# wally.net
KiCad netlist of a schematic drawn in EAGLE
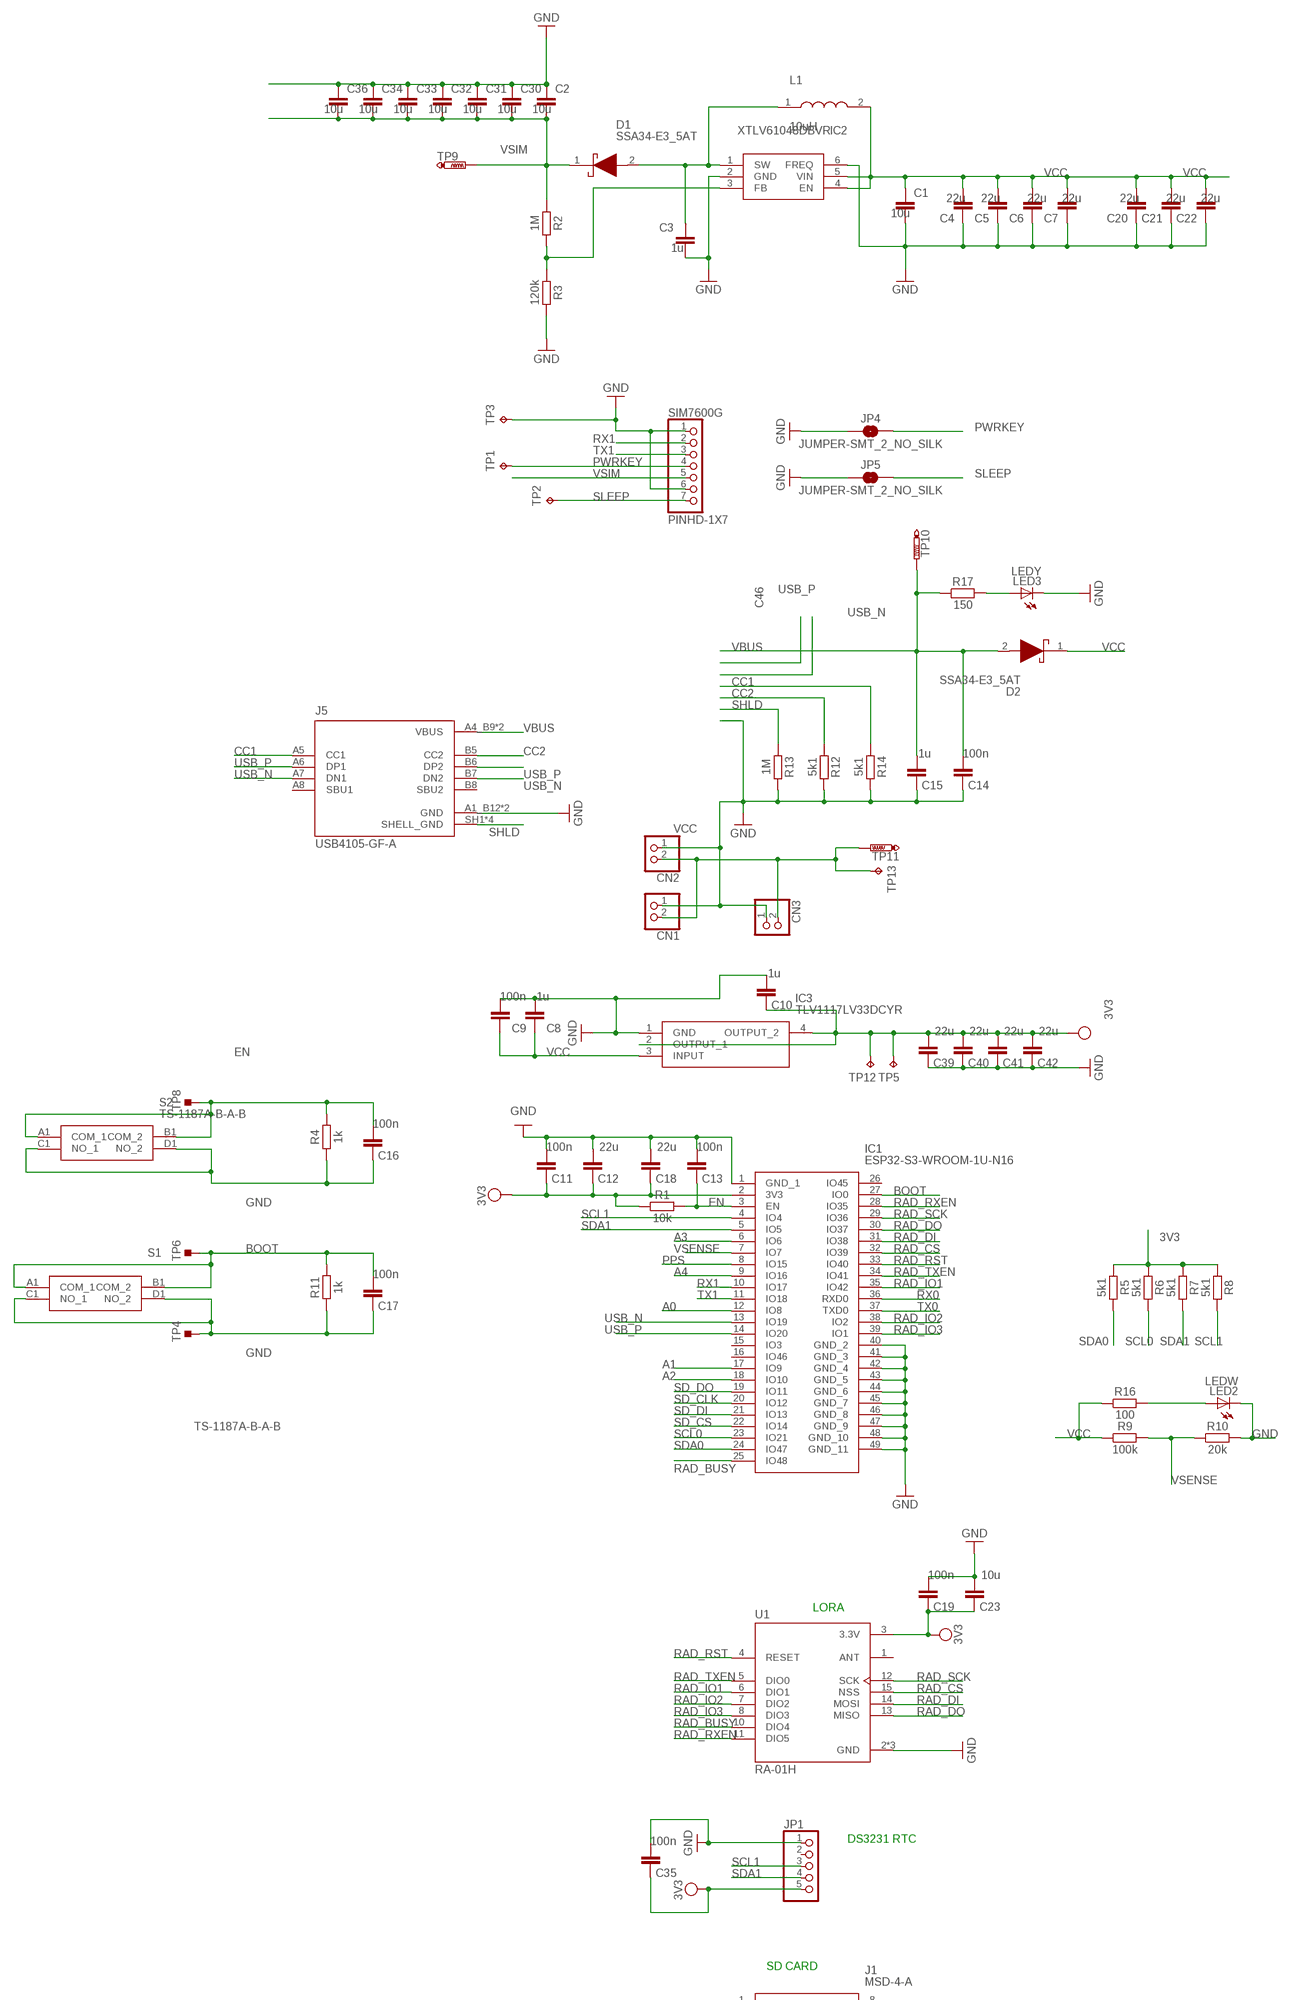
[diagram p0: schematic, sheet 1, part 1 of 2]
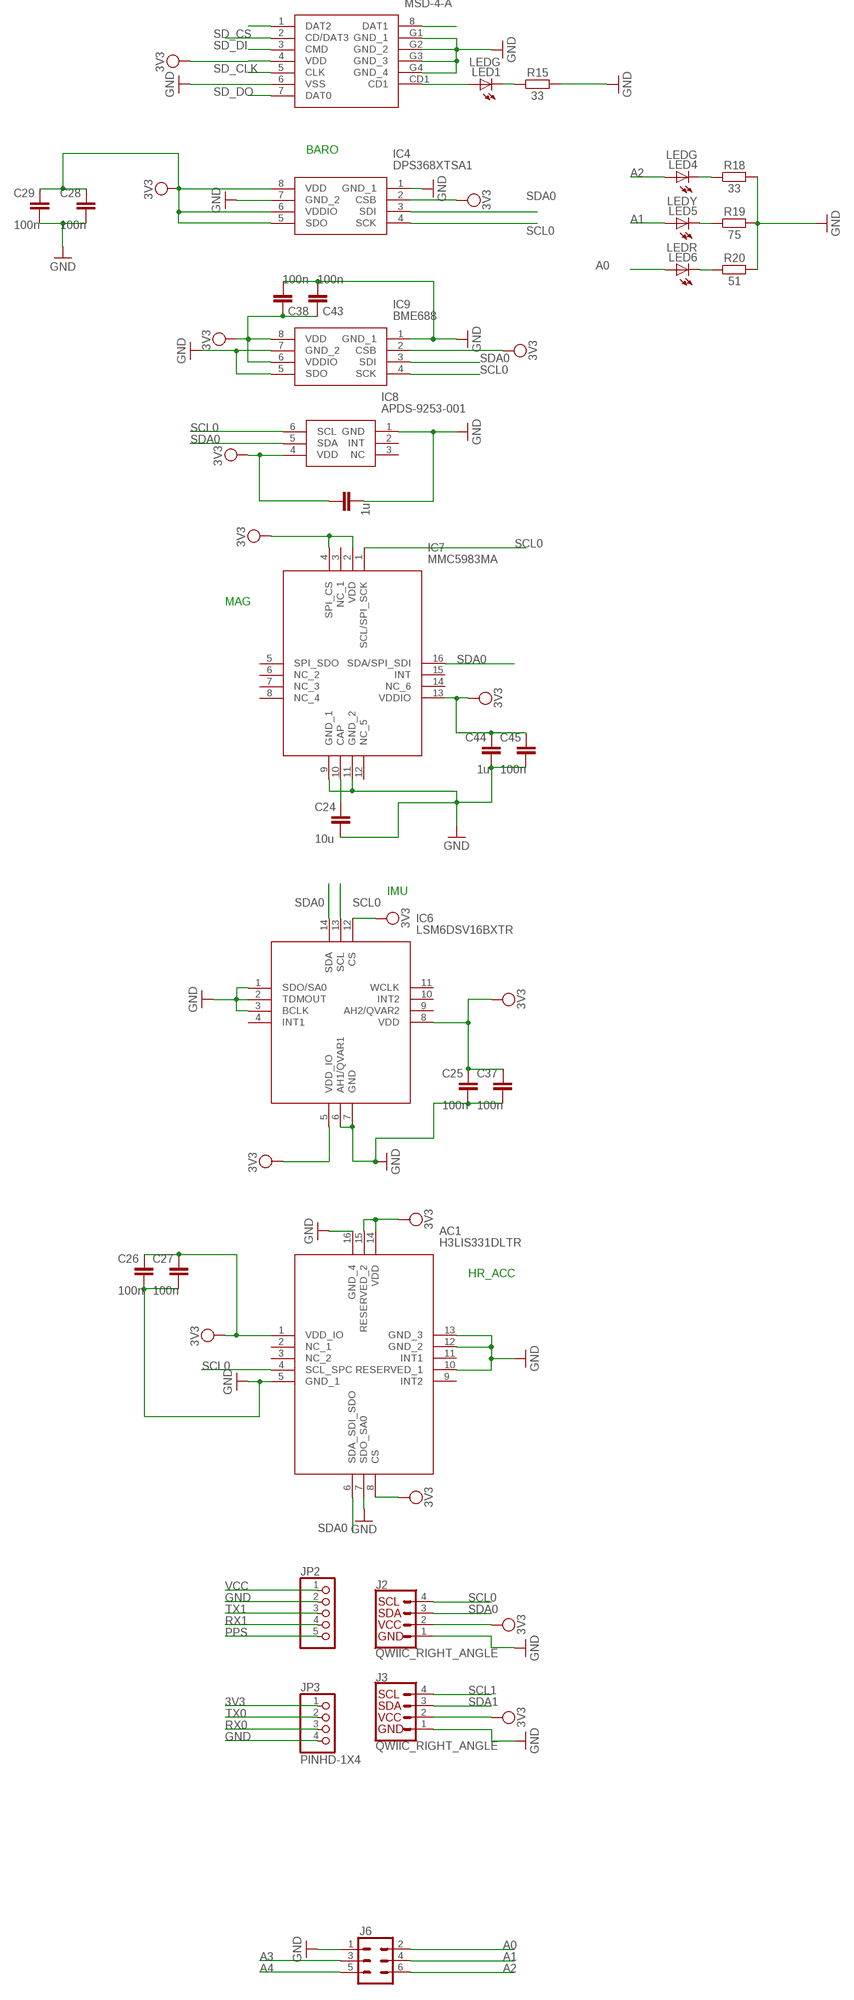
[diagram p1: schematic, sheet 1, part 2 of 2]

(export (version "E")
  (design (tool "Eeschema 10.0.6"))
  (components
    (comp (ref "AC1")
      (value "H3LIS331DLTR")
      (footprint "eagle-import:LIS3DHTR")
      (fields (field (name "MOUSER_PART_NUMBER") "511-H3LIS331DLTR"))
      (libsource (lib "eagle-import") (part "H3LIS331DLTR"))
    )
    (comp (ref "C1")
      (value "10u")
      (footprint "eagle-import:CAPC1005X60")
      (libsource (lib "eagle-import") (part "CCHIP-0402(1005-METRIC)_"))
    )
    (comp (ref "C2")
      (value "10u")
      (footprint "eagle-import:CAPC1608X85")
      (libsource (lib "eagle-import") (part "CCHIP-0603(1608-METRIC)_"))
    )
    (comp (ref "C3")
      (value "1u")
      (footprint "eagle-import:CAPC1005X60")
      (libsource (lib "eagle-import") (part "CCHIP-0402(1005-METRIC)_"))
    )
    (comp (ref "C4")
      (value "22u")
      (footprint "eagle-import:CAPC1608X85")
      (libsource (lib "eagle-import") (part "CCHIP-0603(1608-METRIC)_"))
    )
    (comp (ref "C5")
      (value "22u")
      (footprint "eagle-import:CAPC1608X85")
      (libsource (lib "eagle-import") (part "CCHIP-0603(1608-METRIC)_"))
    )
    (comp (ref "C6")
      (value "22u")
      (footprint "eagle-import:CAPC1608X85")
      (libsource (lib "eagle-import") (part "CCHIP-0603(1608-METRIC)_"))
    )
    (comp (ref "C7")
      (value "22u")
      (footprint "eagle-import:CAPC1608X85")
      (libsource (lib "eagle-import") (part "CCHIP-0603(1608-METRIC)_"))
    )
    (comp (ref "C8")
      (value "1u")
      (footprint "eagle-import:CAPC1005X60")
      (libsource (lib "eagle-import") (part "CCHIP-0402(1005-METRIC)_"))
    )
    (comp (ref "C9")
      (value "100n")
      (footprint "eagle-import:CAPC1005X60")
      (libsource (lib "eagle-import") (part "CCHIP-0402(1005-METRIC)_"))
    )
    (comp (ref "C10")
      (value "1u")
      (footprint "eagle-import:CAPC1005X60")
      (libsource (lib "eagle-import") (part "CCHIP-0402(1005-METRIC)_"))
    )
    (comp (ref "C11")
      (value "100n")
      (footprint "eagle-import:CAPC1005X60")
      (libsource (lib "eagle-import") (part "CCHIP-0402(1005-METRIC)_"))
    )
    (comp (ref "C12")
      (value "22u")
      (footprint "eagle-import:CAPC1608X85")
      (libsource (lib "eagle-import") (part "CCHIP-0603(1608-METRIC)_"))
    )
    (comp (ref "C13")
      (value "100n")
      (footprint "eagle-import:CAPC1005X60")
      (libsource (lib "eagle-import") (part "CCHIP-0402(1005-METRIC)_"))
    )
    (comp (ref "C14")
      (value "100n")
      (footprint "eagle-import:CAPC1005X60")
      (libsource (lib "eagle-import") (part "CCHIP-0402(1005-METRIC)_"))
    )
    (comp (ref "C15")
      (value "1u")
      (footprint "eagle-import:CAPC1005X60")
      (libsource (lib "eagle-import") (part "CCHIP-0402(1005-METRIC)_"))
    )
    (comp (ref "C16")
      (value "100n")
      (footprint "eagle-import:CAPC1005X60")
      (libsource (lib "eagle-import") (part "CCHIP-0402(1005-METRIC)_"))
    )
    (comp (ref "C17")
      (value "100n")
      (footprint "eagle-import:CAPC1005X60")
      (libsource (lib "eagle-import") (part "CCHIP-0402(1005-METRIC)_"))
    )
    (comp (ref "C18")
      (value "22u")
      (footprint "eagle-import:CAPC1608X85")
      (libsource (lib "eagle-import") (part "CCHIP-0603(1608-METRIC)_"))
    )
    (comp (ref "C19")
      (value "100n")
      (footprint "eagle-import:CAPC1005X60")
      (libsource (lib "eagle-import") (part "CCHIP-0402(1005-METRIC)_"))
    )
    (comp (ref "C20")
      (value "22u")
      (footprint "eagle-import:CAPC1608X85")
      (libsource (lib "eagle-import") (part "CCHIP-0603(1608-METRIC)_"))
    )
    (comp (ref "C21")
      (value "22u")
      (footprint "eagle-import:CAPC1608X85")
      (libsource (lib "eagle-import") (part "CCHIP-0603(1608-METRIC)_"))
    )
    (comp (ref "C22")
      (value "22u")
      (footprint "eagle-import:CAPC1608X85")
      (libsource (lib "eagle-import") (part "CCHIP-0603(1608-METRIC)_"))
    )
    (comp (ref "C23")
      (value "10u")
      (footprint "eagle-import:CAPC1005X60")
      (libsource (lib "eagle-import") (part "CCHIP-0402(1005-METRIC)_"))
    )
    (comp (ref "C24")
      (value "10u")
      (footprint "eagle-import:CAPC1005X60")
      (libsource (lib "eagle-import") (part "CCHIP-0402(1005-METRIC)_"))
    )
    (comp (ref "C25")
      (value "100n")
      (footprint "eagle-import:CAPC1005X60")
      (libsource (lib "eagle-import") (part "CCHIP-0402(1005-METRIC)_"))
    )
    (comp (ref "C26")
      (value "100n")
      (footprint "eagle-import:CAPC1005X60")
      (libsource (lib "eagle-import") (part "CCHIP-0402(1005-METRIC)_"))
    )
    (comp (ref "C27")
      (value "100n")
      (footprint "eagle-import:CAPC1005X60")
      (libsource (lib "eagle-import") (part "CCHIP-0402(1005-METRIC)_"))
    )
    (comp (ref "C28")
      (value "100n")
      (footprint "eagle-import:CAPC1005X60")
      (libsource (lib "eagle-import") (part "CCHIP-0402(1005-METRIC)_"))
    )
    (comp (ref "C29")
      (value "100n")
      (footprint "eagle-import:CAPC1005X60")
      (libsource (lib "eagle-import") (part "CCHIP-0402(1005-METRIC)_"))
    )
    (comp (ref "C30")
      (value "10u")
      (footprint "eagle-import:CAPC1608X85")
      (libsource (lib "eagle-import") (part "CCHIP-0603(1608-METRIC)_"))
    )
    (comp (ref "C31")
      (value "10u")
      (footprint "eagle-import:CAPC1608X85")
      (libsource (lib "eagle-import") (part "CCHIP-0603(1608-METRIC)_"))
    )
    (comp (ref "C32")
      (value "10u")
      (footprint "eagle-import:CAPC1608X85")
      (libsource (lib "eagle-import") (part "CCHIP-0603(1608-METRIC)_"))
    )
    (comp (ref "C33")
      (value "10u")
      (footprint "eagle-import:CAPC1608X85")
      (libsource (lib "eagle-import") (part "CCHIP-0603(1608-METRIC)_"))
    )
    (comp (ref "C34")
      (value "10u")
      (footprint "eagle-import:CAPC1608X85")
      (libsource (lib "eagle-import") (part "CCHIP-0603(1608-METRIC)_"))
    )
    (comp (ref "C35")
      (value "100n")
      (footprint "eagle-import:CAPC1005X60")
      (libsource (lib "eagle-import") (part "CCHIP-0402(1005-METRIC)_"))
    )
    (comp (ref "C36")
      (value "10u")
      (footprint "eagle-import:CAPC1608X85")
      (libsource (lib "eagle-import") (part "CCHIP-0603(1608-METRIC)_"))
    )
    (comp (ref "C37")
      (value "100n")
      (footprint "eagle-import:CAPC1005X60")
      (libsource (lib "eagle-import") (part "CCHIP-0402(1005-METRIC)_"))
    )
    (comp (ref "C38")
      (value "100n")
      (footprint "eagle-import:CAPC1005X60")
      (libsource (lib "eagle-import") (part "CCHIP-0402(1005-METRIC)_"))
    )
    (comp (ref "C39")
      (value "22u")
      (footprint "eagle-import:CAPC1608X85")
      (libsource (lib "eagle-import") (part "CCHIP-0603(1608-METRIC)_"))
    )
    (comp (ref "C40")
      (value "22u")
      (footprint "eagle-import:CAPC1608X85")
      (libsource (lib "eagle-import") (part "CCHIP-0603(1608-METRIC)_"))
    )
    (comp (ref "C41")
      (value "22u")
      (footprint "eagle-import:CAPC1608X85")
      (libsource (lib "eagle-import") (part "CCHIP-0603(1608-METRIC)_"))
    )
    (comp (ref "C42")
      (value "22u")
      (footprint "eagle-import:CAPC1608X85")
      (libsource (lib "eagle-import") (part "CCHIP-0603(1608-METRIC)_"))
    )
    (comp (ref "C43")
      (value "100n")
      (footprint "eagle-import:CAPC1005X60")
      (libsource (lib "eagle-import") (part "CCHIP-0402(1005-METRIC)_"))
    )
    (comp (ref "C44")
      (value "1u")
      (footprint "eagle-import:CAPC1005X60")
      (libsource (lib "eagle-import") (part "CCHIP-0402(1005-METRIC)_"))
    )
    (comp (ref "C45")
      (value "100n")
      (footprint "eagle-import:CAPC1005X60")
      (libsource (lib "eagle-import") (part "CCHIP-0402(1005-METRIC)_"))
    )
    (comp (ref "C46")
      (value "1u")
      (footprint "eagle-import:CAPC1005X60")
      (libsource (lib "eagle-import") (part "CCHIP-0402(1005-METRIC)_"))
    )
    (comp (ref "CN1")
      (value "JST_2PIN-THM-RA")
      (footprint "eagle-import:JST-PH-2-THM-RA")
      (libsource (lib "eagle-import") (part "JST_2PIN-THM-RA"))
    )
    (comp (ref "CN2")
      (value "JST_2PIN-THM-RA")
      (footprint "eagle-import:JST-PH-2-THM-RA")
      (libsource (lib "eagle-import") (part "JST_2PIN-THM-RA"))
    )
    (comp (ref "CN3")
      (value "JST_2PIN-THM-RA")
      (footprint "eagle-import:JST-PH-2-THM-RA")
      (libsource (lib "eagle-import") (part "JST_2PIN-THM-RA"))
    )
    (comp (ref "D1")
      (value "SSA34-E3_5AT")
      (footprint "eagle-import:DIOM5127X229N")
      (fields
        (field (name "ARROW_PART_NUMBER") "SSA34-E3/5AT")
        (field (name "MOUSER_PART_NUMBER") "625-SSA34-E3/5AT")
      )
      (libsource (lib "eagle-import") (part "SSA34-E3_5AT"))
    )
    (comp (ref "D2")
      (value "SSA34-E3_5AT")
      (footprint "eagle-import:DIOM5127X229N")
      (fields
        (field (name "ARROW_PART_NUMBER") "SSA34-E3/5AT")
        (field (name "MOUSER_PART_NUMBER") "625-SSA34-E3/5AT")
      )
      (libsource (lib "eagle-import") (part "SSA34-E3_5AT"))
    )
    (comp (ref "IC1")
      (value "ESP32-S3-WROOM-1U-N16")
      (footprint "eagle-import:ESP32S3WROOM1UN16")
      (fields (field (name "MOUSER_PART_NUMBER") "356-ESP32S3WROM1UN16"))
      (libsource (lib "eagle-import") (part "ESP32-S3-WROOM-1U-N16"))
    )
    (comp (ref "IC2")
      (value "XTLV61048DBVR")
      (footprint "eagle-import:SOT95P280X145-6N")
      (libsource (lib "eagle-import") (part "XTLV61048DBVR"))
    )
    (comp (ref "IC3")
      (value "TLV1117LV33DCYR")
      (footprint "eagle-import:SOT230P700X180-4N")
      (fields (field (name "MOUSER_PART_NUMBER") "595-TLV1117LV33DCYR"))
      (libsource (lib "eagle-import") (part "TLV1117LV33DCYR"))
    )
    (comp (ref "IC4")
      (value "DPS368XTSA1")
      (footprint "eagle-import:DPS368XTSA1")
      (fields (field (name "MOUSER_PART_NUMBER") "726-DPS368XTSA1"))
      (libsource (lib "eagle-import") (part "DPS368XTSA1"))
    )
    (comp (ref "IC6")
      (value "LSM6DSV16BXTR")
      (footprint "eagle-import:LSM6DSV16BXTR")
      (fields (field (name "MOUSER_PART_NUMBER") "511-LSM6DSV16BXTR"))
      (libsource (lib "eagle-import") (part "LSM6DSV16BXTR"))
    )
    (comp (ref "IC7")
      (value "MMC5983MA")
      (footprint "eagle-import:MMC5983MA")
      (fields (field (name "MOUSER_PART_NUMBER") "438-MMC5983MA"))
      (libsource (lib "eagle-import") (part "MMC5983MA"))
    )
    (comp (ref "IC8")
      (value "APDS-9253-001")
      (footprint "eagle-import:APDS9253001")
      (fields (field (name "MOUSER_PART_NUMBER") "630-APDS-9253-001"))
      (libsource (lib "eagle-import") (part "APDS-9253-001"))
    )
    (comp (ref "IC9")
      (value "BME688")
      (footprint "eagle-import:BME688")
      (fields (field (name "MOUSER_PART_NUMBER") "262-BME688"))
      (libsource (lib "eagle-import") (part "BME688"))
    )
    (comp (ref "J1")
      (value "MSD-4-A")
      (footprint "eagle-import:MSD4A")
      (fields (field (name "MOUSER_PART_NUMBER") "179-MSD-4-A"))
      (libsource (lib "eagle-import") (part "MSD-4-A"))
    )
    (comp (ref "J2")
      (value "QWIIC_RIGHT_ANGLE")
      (footprint "eagle-import:JST04_1MM_RA")
      (libsource (lib "eagle-import") (part "QWIIC_CONNECTORJS-1MM"))
    )
    (comp (ref "J3")
      (value "QWIIC_RIGHT_ANGLE")
      (footprint "eagle-import:JST04_1MM_RA")
      (libsource (lib "eagle-import") (part "QWIIC_CONNECTORJS-1MM"))
    )
    (comp (ref "J5")
      (value "USB4105-GF-A")
      (footprint "eagle-import:GCT_USB4105-GF-A")
      (fields
        (field (name "DIGIKEY_PART_NUMBER") "2073-USB4105-GF-ATR-ND")
        (field (name "MF") "Global Connector Technology")
        (field (name "MP") "USB4105GFA")
      )
      (libsource (lib "eagle-import") (part "USB4105-GF-A"))
    )
    (comp (ref "J6")
      (value "FEMALE 2x3")
      (footprint "eagle-import:2X3-NS")
      (libsource (lib "eagle-import") (part "CONN_03X2NO_SILK"))
    )
    (comp (ref "JP1")
      (value "PINHD-1X5")
      (footprint "eagle-import:1X05")
      (libsource (lib "eagle-import") (part "PINHD-1X5"))
    )
    (comp (ref "JP2")
      (value "PINHD-1X5")
      (footprint "eagle-import:1X05")
      (libsource (lib "eagle-import") (part "PINHD-1X5"))
    )
    (comp (ref "JP3")
      (value "PINHD-1X4")
      (footprint "eagle-import:1X04")
      (fields (field (name "MANUFACTURER") "Generic"))
      (libsource (lib "eagle-import") (part "PINHD-1X4"))
    )
    (comp (ref "JP4")
      (value "JUMPER-SMT_2_NO_SILK")
      (footprint "eagle-import:SMT-JUMPER_2_NO_SILK")
      (libsource (lib "eagle-import") (part "JUMPER-SMT_2_NO_SILK"))
    )
    (comp (ref "JP5")
      (value "JUMPER-SMT_2_NO_SILK")
      (footprint "eagle-import:SMT-JUMPER_2_NO_SILK")
      (libsource (lib "eagle-import") (part "JUMPER-SMT_2_NO_SILK"))
    )
    (comp (ref "L1")
      (value "10uH")
      (footprint "eagle-import:BMRF00060630100MA1")
      (fields (field (name "MANUFACTURER_PART_NUMBER") "BMRF00060630100MA1"))
      (libsource (lib "eagle-import") (part "BMRF00060630100MA1"))
    )
    (comp (ref "LED1")
      (value "LEDG")
      (footprint "eagle-import:CHIPLED_0805")
      (libsource (lib "eagle-import") (part "LEDCHIPLED_0805"))
    )
    (comp (ref "LED2")
      (value "LEDW")
      (footprint "eagle-import:CHIPLED_0805")
      (libsource (lib "eagle-import") (part "LEDCHIPLED_0805"))
    )
    (comp (ref "LED3")
      (value "LEDY")
      (footprint "eagle-import:CHIPLED_0805")
      (libsource (lib "eagle-import") (part "LEDCHIPLED_0805"))
    )
    (comp (ref "LED4")
      (value "LEDG")
      (footprint "eagle-import:CHIPLED_0805")
      (libsource (lib "eagle-import") (part "LEDCHIPLED_0805"))
    )
    (comp (ref "LED5")
      (value "LEDY")
      (footprint "eagle-import:CHIPLED_0805")
      (libsource (lib "eagle-import") (part "LEDCHIPLED_0805"))
    )
    (comp (ref "LED6")
      (value "LEDR")
      (footprint "eagle-import:CHIPLED_0805")
      (libsource (lib "eagle-import") (part "LEDCHIPLED_0805"))
    )
    (comp (ref "R1")
      (value "10k")
      (footprint "eagle-import:RESC1005X40")
      (libsource (lib "eagle-import") (part "RCHIP-0402(1005-METRIC)_"))
    )
    (comp (ref "R2")
      (value "1M")
      (footprint "eagle-import:RESC1608X60")
      (libsource (lib "eagle-import") (part "RCHIP-0603(1608-METRIC)_"))
    )
    (comp (ref "R3")
      (value "120k")
      (footprint "eagle-import:RESC1608X60")
      (libsource (lib "eagle-import") (part "RCHIP-0603(1608-METRIC)_"))
    )
    (comp (ref "R4")
      (value "1k")
      (footprint "eagle-import:RESC1005X40")
      (libsource (lib "eagle-import") (part "RCHIP-0402(1005-METRIC)_"))
    )
    (comp (ref "R5")
      (value "5k1")
      (footprint "eagle-import:RESC1005X40")
      (libsource (lib "eagle-import") (part "RCHIP-0402(1005-METRIC)_"))
    )
    (comp (ref "R6")
      (value "5k1")
      (footprint "eagle-import:RESC1005X40")
      (libsource (lib "eagle-import") (part "RCHIP-0402(1005-METRIC)_"))
    )
    (comp (ref "R7")
      (value "5k1")
      (footprint "eagle-import:RESC1005X40")
      (libsource (lib "eagle-import") (part "RCHIP-0402(1005-METRIC)_"))
    )
    (comp (ref "R8")
      (value "5k1")
      (footprint "eagle-import:RESC1005X40")
      (libsource (lib "eagle-import") (part "RCHIP-0402(1005-METRIC)_"))
    )
    (comp (ref "R9")
      (value "100k")
      (footprint "eagle-import:RESC1005X40")
      (libsource (lib "eagle-import") (part "RCHIP-0402(1005-METRIC)_"))
    )
    (comp (ref "R10")
      (value "20k")
      (footprint "eagle-import:RESC1005X40")
      (libsource (lib "eagle-import") (part "RCHIP-0402(1005-METRIC)_"))
    )
    (comp (ref "R11")
      (value "1k")
      (footprint "eagle-import:RESC1005X40")
      (libsource (lib "eagle-import") (part "RCHIP-0402(1005-METRIC)_"))
    )
    (comp (ref "R12")
      (value "5k1")
      (footprint "eagle-import:RESC1608X60")
      (libsource (lib "eagle-import") (part "RCHIP-0603(1608-METRIC)_"))
    )
    (comp (ref "R13")
      (value "1M")
      (footprint "eagle-import:RESC1005X40")
      (libsource (lib "eagle-import") (part "RCHIP-0402(1005-METRIC)_"))
    )
    (comp (ref "R14")
      (value "5k1")
      (footprint "eagle-import:RESC1608X60")
      (libsource (lib "eagle-import") (part "RCHIP-0603(1608-METRIC)_"))
    )
    (comp (ref "R15")
      (value "33")
      (footprint "eagle-import:RESC1005X40")
      (libsource (lib "eagle-import") (part "RCHIP-0402(1005-METRIC)_"))
    )
    (comp (ref "R16")
      (value "100")
      (footprint "eagle-import:RESC1005X40")
      (libsource (lib "eagle-import") (part "RCHIP-0402(1005-METRIC)_"))
    )
    (comp (ref "R17")
      (value "150")
      (footprint "eagle-import:RESC1608X60")
      (libsource (lib "eagle-import") (part "RCHIP-0603(1608-METRIC)_"))
    )
    (comp (ref "R18")
      (value "33")
      (footprint "eagle-import:RESC1005X40")
      (libsource (lib "eagle-import") (part "RCHIP-0402(1005-METRIC)_"))
    )
    (comp (ref "R19")
      (value "75")
      (footprint "eagle-import:RESC1608X60")
      (libsource (lib "eagle-import") (part "RCHIP-0603(1608-METRIC)_"))
    )
    (comp (ref "R20")
      (value "51")
      (footprint "eagle-import:RESC1608X60")
      (libsource (lib "eagle-import") (part "RCHIP-0603(1608-METRIC)_"))
    )
    (comp (ref "S1")
      (value "TS-1187A-B-A-B")
      (footprint "eagle-import:TS1187ABAB")
      (libsource (lib "eagle-import") (part "TS-1187A-B-A-B"))
    )
    (comp (ref "S2")
      (value "TS-1187A-B-A-B")
      (footprint "eagle-import:TS1187ABAB")
      (libsource (lib "eagle-import") (part "TS-1187A-B-A-B"))
    )
    (comp (ref "SIM7600G")
      (value "PINHD-1X7")
      (footprint "eagle-import:1X07")
      (fields (field (name "MANUFACTURER") "Generic"))
      (libsource (lib "eagle-import") (part "PINHD-1X7"))
    )
    (comp (ref "TP1")
      (value "TPPAD1-13")
      (footprint "eagle-import:P1-13")
      (libsource (lib "eagle-import") (part "TPPAD1-13"))
    )
    (comp (ref "TP2")
      (value "TPPAD1-13")
      (footprint "eagle-import:P1-13")
      (libsource (lib "eagle-import") (part "TPPAD1-13"))
    )
    (comp (ref "TP3")
      (value "TPPAD1-13")
      (footprint "eagle-import:P1-13")
      (libsource (lib "eagle-import") (part "TPPAD1-13"))
    )
    (comp (ref "TP4")
      (value "TESTPOINT_TPS-PAD-036")
      (footprint "eagle-import:TESTPOINT_PAD-036")
      (libsource (lib "eagle-import") (part "TESTPOINT_TPS-PAD-036"))
    )
    (comp (ref "TP5")
      (value "TPPAD1-13")
      (footprint "eagle-import:P1-13")
      (libsource (lib "eagle-import") (part "TPPAD1-13"))
    )
    (comp (ref "TP6")
      (value "TESTPOINT_TPS-PAD-036")
      (footprint "eagle-import:TESTPOINT_PAD-036")
      (libsource (lib "eagle-import") (part "TESTPOINT_TPS-PAD-036"))
    )
    (comp (ref "TP8")
      (value "TESTPOINT_TPS-PAD-036")
      (footprint "eagle-import:TESTPOINT_PAD-036")
      (libsource (lib "eagle-import") (part "TESTPOINT_TPS-PAD-036"))
    )
    (comp (ref "TP9")
      (value "PTR1PAD1-13")
      (footprint "eagle-import:P1-13")
      (libsource (lib "eagle-import") (part "PTR1PAD1-13"))
    )
    (comp (ref "TP10")
      (value "PTR1PAD1-13")
      (footprint "eagle-import:P1-13")
      (libsource (lib "eagle-import") (part "PTR1PAD1-13"))
    )
    (comp (ref "TP11")
      (value "PTR1PAD1-13")
      (footprint "eagle-import:P1-13")
      (libsource (lib "eagle-import") (part "PTR1PAD1-13"))
    )
    (comp (ref "TP12")
      (value "TPPAD1-13")
      (footprint "eagle-import:P1-13")
      (libsource (lib "eagle-import") (part "TPPAD1-13"))
    )
    (comp (ref "TP13")
      (value "TPPAD1-13")
      (footprint "eagle-import:P1-13")
      (libsource (lib "eagle-import") (part "TPPAD1-13"))
    )
    (comp (ref "U1")
      (value "RA-01H")
      (footprint "eagle-import:XCVR_RA-01H")
      (fields (field (name "MF") "AI-Thinker"))
      (libsource (lib "eagle-import") (part "RA-01H"))
    )
  )
  (nets
    (net (code "1") (name "/A0") (class "Default")
      (node (ref "IC1") (pin "12") (pinfunction "IO8_12") (pintype "bidirectional"))
      (node (ref "J6") (pin "2") (pinfunction "2_2") (pintype "bidirectional"))
      (node (ref "LED6") (pin "A") (pinfunction "A_A") (pintype "passive"))
    )
    (net (code "2") (name "/A1") (class "Default")
      (node (ref "IC1") (pin "17") (pinfunction "IO9_17") (pintype "bidirectional"))
      (node (ref "J6") (pin "4") (pinfunction "4_4") (pintype "bidirectional"))
      (node (ref "LED5") (pin "A") (pinfunction "A_A") (pintype "passive"))
    )
    (net (code "3") (name "/A2") (class "Default")
      (node (ref "IC1") (pin "18") (pinfunction "IO10_18") (pintype "bidirectional"))
      (node (ref "J6") (pin "6") (pinfunction "6_6") (pintype "bidirectional"))
      (node (ref "LED4") (pin "A") (pinfunction "A_A") (pintype "passive"))
    )
    (net (code "4") (name "/A3") (class "Default")
      (node (ref "IC1") (pin "6") (pinfunction "IO6_6") (pintype "bidirectional"))
      (node (ref "J6") (pin "3") (pinfunction "3_3") (pintype "bidirectional"))
    )
    (net (code "5") (name "/A4") (class "Default")
      (node (ref "IC1") (pin "9") (pinfunction "IO16_9") (pintype "bidirectional"))
      (node (ref "J6") (pin "5") (pinfunction "5_5") (pintype "bidirectional"))
    )
    (net (code "6") (name "/BOOT") (class "Default")
      (node (ref "C17") (pin "2") (pinfunction "2_2") (pintype "passive"))
      (node (ref "IC1") (pin "27") (pinfunction "IO0_27") (pintype "bidirectional"))
      (node (ref "R11") (pin "2") (pinfunction "2_2") (pintype "passive"))
      (node (ref "S1") (pin "A1") (pinfunction "COM_1_A1") (pintype "bidirectional"))
      (node (ref "S1") (pin "B1") (pinfunction "COM_2_B1") (pintype "bidirectional"))
      (node (ref "TP6") (pin "1") (pinfunction "TP_1") (pintype "passive"))
    )
    (net (code "7") (name "/CC1") (class "Default")
      (node (ref "J5") (pin "A5") (pinfunction "CC1_A5") (pintype "bidirectional"))
      (node (ref "R14") (pin "1") (pinfunction "1_1") (pintype "passive"))
    )
    (net (code "8") (name "/CC2") (class "Default")
      (node (ref "J5") (pin "B5") (pinfunction "CC2_B5") (pintype "bidirectional"))
      (node (ref "R12") (pin "1") (pinfunction "1_1") (pintype "passive"))
    )
    (net (code "9") (name "/EN") (class "Default")
      (node (ref "C13") (pin "1") (pinfunction "1_1") (pintype "passive"))
      (node (ref "C16") (pin "2") (pinfunction "2_2") (pintype "passive"))
      (node (ref "IC1") (pin "3") (pinfunction "EN_3") (pintype "bidirectional"))
      (node (ref "R1") (pin "2") (pinfunction "2_2") (pintype "passive"))
      (node (ref "R4") (pin "2") (pinfunction "2_2") (pintype "passive"))
      (node (ref "S2") (pin "A1") (pinfunction "COM_1_A1") (pintype "bidirectional"))
      (node (ref "S2") (pin "B1") (pinfunction "COM_2_B1") (pintype "bidirectional"))
      (node (ref "TP8") (pin "1") (pinfunction "TP_1") (pintype "passive"))
    )
    (net (code "10") (name "/PPS") (class "Default")
      (node (ref "IC1") (pin "8") (pinfunction "IO15_8") (pintype "bidirectional"))
      (node (ref "JP2") (pin "5") (pinfunction "5_5") (pintype "passive"))
    )
    (net (code "11") (name "/PWRKEY") (class "Default")
      (node (ref "JP4") (pin "2") (pinfunction "2_2") (pintype "passive"))
      (node (ref "SIM7600G") (pin "4") (pinfunction "4_4") (pintype "passive"))
      (node (ref "TP1") (pin "TP") (pinfunction "TP_TP") (pintype "input"))
    )
    (net (code "12") (name "/RAD_BUSY") (class "Default")
      (node (ref "IC1") (pin "25") (pinfunction "IO48_25") (pintype "bidirectional"))
      (node (ref "U1") (pin "10") (pinfunction "DIO4_10") (pintype "bidirectional"))
    )
    (net (code "13") (name "/RAD_CS") (class "Default")
      (node (ref "IC1") (pin "32") (pinfunction "IO39_32") (pintype "bidirectional"))
      (node (ref "U1") (pin "15") (pinfunction "NSS_15") (pintype "input"))
    )
    (net (code "14") (name "/RAD_DI") (class "Default")
      (node (ref "IC1") (pin "31") (pinfunction "IO38_31") (pintype "bidirectional"))
      (node (ref "U1") (pin "14") (pinfunction "MOSI_14") (pintype "input"))
    )
    (net (code "15") (name "/RAD_DO") (class "Default")
      (node (ref "IC1") (pin "30") (pinfunction "IO37_30") (pintype "bidirectional"))
      (node (ref "U1") (pin "13") (pinfunction "MISO_13") (pintype "output"))
    )
    (net (code "16") (name "/RAD_IO1") (class "Default")
      (node (ref "IC1") (pin "35") (pinfunction "IO42_35") (pintype "bidirectional"))
      (node (ref "U1") (pin "6") (pinfunction "DIO1_6") (pintype "bidirectional"))
    )
    (net (code "17") (name "/RAD_IO2") (class "Default")
      (node (ref "IC1") (pin "38") (pinfunction "IO2_38") (pintype "bidirectional"))
      (node (ref "U1") (pin "7") (pinfunction "DIO2_7") (pintype "bidirectional"))
    )
    (net (code "18") (name "/RAD_IO3") (class "Default")
      (node (ref "IC1") (pin "39") (pinfunction "IO1_39") (pintype "bidirectional"))
      (node (ref "U1") (pin "8") (pinfunction "DIO3_8") (pintype "bidirectional"))
    )
    (net (code "19") (name "/RAD_RST") (class "Default")
      (node (ref "IC1") (pin "33") (pinfunction "IO40_33") (pintype "bidirectional"))
      (node (ref "U1") (pin "4") (pinfunction "RESET_4") (pintype "input"))
    )
    (net (code "20") (name "/RAD_RXEN") (class "Default")
      (node (ref "IC1") (pin "28") (pinfunction "IO35_28") (pintype "bidirectional"))
      (node (ref "U1") (pin "11") (pinfunction "DIO5_11") (pintype "bidirectional"))
    )
    (net (code "21") (name "/RAD_SCK") (class "Default")
      (node (ref "IC1") (pin "29") (pinfunction "IO36_29") (pintype "bidirectional"))
      (node (ref "U1") (pin "12") (pinfunction "SCK_12") (pintype "input"))
    )
    (net (code "22") (name "/RAD_TXEN") (class "Default")
      (node (ref "IC1") (pin "34") (pinfunction "IO41_34") (pintype "bidirectional"))
      (node (ref "U1") (pin "5") (pinfunction "DIO0_5") (pintype "bidirectional"))
    )
    (net (code "23") (name "/RX0") (class "Default")
      (node (ref "IC1") (pin "36") (pinfunction "RXD0_36") (pintype "bidirectional"))
      (node (ref "JP3") (pin "3") (pinfunction "3_3") (pintype "passive"))
    )
    (net (code "24") (name "/RX1") (class "Default")
      (node (ref "IC1") (pin "10") (pinfunction "IO17_10") (pintype "bidirectional"))
      (node (ref "JP2") (pin "4") (pinfunction "4_4") (pintype "passive"))
      (node (ref "SIM7600G") (pin "2") (pinfunction "2_2") (pintype "passive"))
    )
    (net (code "25") (name "/SCL0") (class "Default")
      (node (ref "AC1") (pin "4") (pinfunction "SCL_SPC_4") (pintype "bidirectional"))
      (node (ref "IC1") (pin "23") (pinfunction "IO21_23") (pintype "bidirectional"))
      (node (ref "IC4") (pin "4") (pinfunction "SCK_4") (pintype "bidirectional"))
      (node (ref "IC6") (pin "13") (pinfunction "SCL_13") (pintype "bidirectional"))
      (node (ref "IC7") (pin "1") (pinfunction "SCL/SPI_SCK_1") (pintype "bidirectional"))
      (node (ref "IC8") (pin "6") (pinfunction "SCL_6") (pintype "bidirectional"))
      (node (ref "IC9") (pin "4") (pinfunction "SCK_4") (pintype "bidirectional"))
      (node (ref "J2") (pin "4") (pinfunction "4_4") (pintype "passive"))
      (node (ref "R6") (pin "2") (pinfunction "2_2") (pintype "passive"))
    )
    (net (code "26") (name "/SCL1") (class "Default")
      (node (ref "IC1") (pin "4") (pinfunction "IO4_4") (pintype "bidirectional"))
      (node (ref "J3") (pin "4") (pinfunction "4_4") (pintype "passive"))
      (node (ref "JP1") (pin "3") (pinfunction "3_3") (pintype "passive"))
      (node (ref "R8") (pin "2") (pinfunction "2_2") (pintype "passive"))
    )
    (net (code "27") (name "/SDA0") (class "Default")
      (node (ref "AC1") (pin "6") (pinfunction "SDA_SDI_SDO_6") (pintype "bidirectional"))
      (node (ref "IC1") (pin "24") (pinfunction "IO47_24") (pintype "bidirectional"))
      (node (ref "IC4") (pin "3") (pinfunction "SDI_3") (pintype "bidirectional"))
      (node (ref "IC6") (pin "14") (pinfunction "SDA_14") (pintype "bidirectional"))
      (node (ref "IC7") (pin "16") (pinfunction "SDA/SPI_SDI_16") (pintype "bidirectional"))
      (node (ref "IC8") (pin "5") (pinfunction "SDA_5") (pintype "bidirectional"))
      (node (ref "IC9") (pin "3") (pinfunction "SDI_3") (pintype "bidirectional"))
      (node (ref "J2") (pin "3") (pinfunction "3_3") (pintype "passive"))
      (node (ref "R5") (pin "2") (pinfunction "2_2") (pintype "passive"))
    )
    (net (code "28") (name "/SDA1") (class "Default")
      (node (ref "IC1") (pin "5") (pinfunction "IO5_5") (pintype "bidirectional"))
      (node (ref "J3") (pin "3") (pinfunction "3_3") (pintype "passive"))
      (node (ref "JP1") (pin "4") (pinfunction "4_4") (pintype "passive"))
      (node (ref "R7") (pin "2") (pinfunction "2_2") (pintype "passive"))
    )
    (net (code "29") (name "/SD_CLK") (class "Default")
      (node (ref "IC1") (pin "20") (pinfunction "IO12_20") (pintype "bidirectional"))
      (node (ref "J1") (pin "5") (pinfunction "CLK_5") (pintype "bidirectional"))
    )
    (net (code "30") (name "/SD_CS") (class "Default")
      (node (ref "IC1") (pin "22") (pinfunction "IO14_22") (pintype "bidirectional"))
      (node (ref "J1") (pin "2") (pinfunction "CD/DAT3_2") (pintype "bidirectional"))
    )
    (net (code "31") (name "/SD_DI") (class "Default")
      (node (ref "IC1") (pin "21") (pinfunction "IO13_21") (pintype "bidirectional"))
      (node (ref "J1") (pin "3") (pinfunction "CMD_3") (pintype "bidirectional"))
    )
    (net (code "32") (name "/SD_DO") (class "Default")
      (node (ref "IC1") (pin "19") (pinfunction "IO11_19") (pintype "bidirectional"))
      (node (ref "J1") (pin "7") (pinfunction "DAT0_7") (pintype "bidirectional"))
    )
    (net (code "33") (name "/SHLD") (class "Default")
      (node (ref "J5") (pin "SH1") (pinfunction "SHELL_GND_SH1") (pintype "power_in"))
      (node (ref "J5") (pin "SH2") (pinfunction "SHELL_GND_SH2") (pintype "power_in"))
      (node (ref "J5") (pin "SH3") (pinfunction "SHELL_GND_SH3") (pintype "power_in"))
      (node (ref "J5") (pin "SH4") (pinfunction "SHELL_GND_SH4") (pintype "power_in"))
      (node (ref "R13") (pin "1") (pinfunction "1_1") (pintype "passive"))
    )
    (net (code "34") (name "/SLEEP") (class "Default")
      (node (ref "JP5") (pin "2") (pinfunction "2_2") (pintype "passive"))
      (node (ref "SIM7600G") (pin "7") (pinfunction "7_7") (pintype "passive"))
      (node (ref "TP2") (pin "TP") (pinfunction "TP_TP") (pintype "input"))
    )
    (net (code "35") (name "/TX0") (class "Default")
      (node (ref "IC1") (pin "37") (pinfunction "TXD0_37") (pintype "bidirectional"))
      (node (ref "JP3") (pin "2") (pinfunction "2_2") (pintype "passive"))
    )
    (net (code "36") (name "/TX1") (class "Default")
      (node (ref "IC1") (pin "11") (pinfunction "IO18_11") (pintype "bidirectional"))
      (node (ref "JP2") (pin "3") (pinfunction "3_3") (pintype "passive"))
      (node (ref "SIM7600G") (pin "3") (pinfunction "3_3") (pintype "passive"))
    )
    (net (code "37") (name "/USB_N") (class "Default")
      (node (ref "IC1") (pin "13") (pinfunction "IO19_13") (pintype "bidirectional"))
      (node (ref "J5") (pin "A7") (pinfunction "DN1_A7") (pintype "bidirectional"))
      (node (ref "J5") (pin "B7") (pinfunction "DN2_B7") (pintype "bidirectional"))
    )
    (net (code "38") (name "/USB_P") (class "Default")
      (node (ref "IC1") (pin "14") (pinfunction "IO20_14") (pintype "bidirectional"))
      (node (ref "J5") (pin "A6") (pinfunction "DP1_A6") (pintype "bidirectional"))
      (node (ref "J5") (pin "B6") (pinfunction "DP2_B6") (pintype "bidirectional"))
    )
    (net (code "39") (name "/VBUS") (class "Default")
      (node (ref "C14") (pin "2") (pinfunction "2_2") (pintype "passive"))
      (node (ref "C15") (pin "2") (pinfunction "2_2") (pintype "passive"))
      (node (ref "D2") (pin "2") (pinfunction "A_2") (pintype "bidirectional"))
      (node (ref "J5") (pin "A4_B9") (pinfunction "VBUS_A4_B9") (pintype "power_in"))
      (node (ref "J5") (pin "B4_A9") (pinfunction "VBUS_B4_A9") (pintype "power_in"))
      (node (ref "R17") (pin "1") (pinfunction "1_1") (pintype "passive"))
      (node (ref "TP10") (pin "TP") (pinfunction "TP_TP") (pintype "input"))
    )
    (net (code "40") (name "/VCC") (class "Default")
      (node (ref "C1") (pin "1") (pinfunction "1_1") (pintype "passive"))
      (node (ref "C20") (pin "2") (pinfunction "2_2") (pintype "passive"))
      (node (ref "C21") (pin "2") (pinfunction "2_2") (pintype "passive"))
      (node (ref "C22") (pin "2") (pinfunction "2_2") (pintype "passive"))
      (node (ref "C4") (pin "2") (pinfunction "2_2") (pintype "passive"))
      (node (ref "C5") (pin "2") (pinfunction "2_2") (pintype "passive"))
      (node (ref "C6") (pin "2") (pinfunction "2_2") (pintype "passive"))
      (node (ref "C7") (pin "2") (pinfunction "2_2") (pintype "passive"))
      (node (ref "C8") (pin "1") (pinfunction "1_1") (pintype "passive"))
      (node (ref "C9") (pin "1") (pinfunction "1_1") (pintype "passive"))
      (node (ref "CN1") (pin "2") (pinfunction "1_2") (pintype "passive"))
      (node (ref "CN2") (pin "2") (pinfunction "1_2") (pintype "passive"))
      (node (ref "CN3") (pin "2") (pinfunction "1_2") (pintype "passive"))
      (node (ref "D2") (pin "1") (pinfunction "K_1") (pintype "bidirectional"))
      (node (ref "IC2") (pin "4") (pinfunction "EN_4") (pintype "bidirectional"))
      (node (ref "IC2") (pin "5") (pinfunction "VIN_5") (pintype "bidirectional"))
      (node (ref "IC3") (pin "3") (pinfunction "INPUT_3") (pintype "bidirectional"))
      (node (ref "JP2") (pin "1") (pinfunction "1_1") (pintype "passive"))
      (node (ref "L1") (pin "2") (pinfunction "2_2") (pintype "bidirectional"))
      (node (ref "R16") (pin "1") (pinfunction "1_1") (pintype "passive"))
      (node (ref "R9") (pin "1") (pinfunction "1_1") (pintype "passive"))
      (node (ref "TP11") (pin "TP") (pinfunction "TP_TP") (pintype "input"))
      (node (ref "TP13") (pin "TP") (pinfunction "TP_TP") (pintype "input"))
    )
    (net (code "41") (name "/VSENSE") (class "Default")
      (node (ref "IC1") (pin "7") (pinfunction "IO7_7") (pintype "bidirectional"))
      (node (ref "R10") (pin "1") (pinfunction "1_1") (pintype "passive"))
      (node (ref "R9") (pin "2") (pinfunction "2_2") (pintype "passive"))
    )
    (net (code "42") (name "/VSIM") (class "Default")
      (node (ref "C2") (pin "2") (pinfunction "2_2") (pintype "passive"))
      (node (ref "C30") (pin "2") (pinfunction "2_2") (pintype "passive"))
      (node (ref "C31") (pin "2") (pinfunction "2_2") (pintype "passive"))
      (node (ref "C32") (pin "2") (pinfunction "2_2") (pintype "passive"))
      (node (ref "C33") (pin "2") (pinfunction "2_2") (pintype "passive"))
      (node (ref "C34") (pin "2") (pinfunction "2_2") (pintype "passive"))
      (node (ref "C36") (pin "2") (pinfunction "2_2") (pintype "passive"))
      (node (ref "D1") (pin "1") (pinfunction "K_1") (pintype "bidirectional"))
      (node (ref "R2") (pin "1") (pinfunction "1_1") (pintype "passive"))
      (node (ref "SIM7600G") (pin "5") (pinfunction "5_5") (pintype "passive"))
      (node (ref "TP9") (pin "TP") (pinfunction "TP_TP") (pintype "input"))
    )
    (net (code "43") (name "3V3") (class "Default")
      (node (ref "AC1") (pin "1") (pinfunction "VDD_IO_1") (pintype "power_in"))
      (node (ref "AC1") (pin "14") (pinfunction "VDD_14") (pintype "power_in"))
      (node (ref "AC1") (pin "15") (pinfunction "RESERVED_2_15") (pintype "bidirectional"))
      (node (ref "AC1") (pin "8") (pinfunction "CS_8") (pintype "input"))
      (node (ref "C10") (pin "1") (pinfunction "1_1") (pintype "passive"))
      (node (ref "C11") (pin "1") (pinfunction "1_1") (pintype "passive"))
      (node (ref "C12") (pin "1") (pinfunction "1_1") (pintype "passive"))
      (node (ref "C18") (pin "1") (pinfunction "1_1") (pintype "passive"))
      (node (ref "C19") (pin "1") (pinfunction "1_1") (pintype "passive"))
      (node (ref "C23") (pin "1") (pinfunction "1_1") (pintype "passive"))
      (node (ref "C25") (pin "1") (pinfunction "1_1") (pintype "passive"))
      (node (ref "C26") (pin "1") (pinfunction "1_1") (pintype "passive"))
      (node (ref "C27") (pin "1") (pinfunction "1_1") (pintype "passive"))
      (node (ref "C28") (pin "1") (pinfunction "1_1") (pintype "passive"))
      (node (ref "C29") (pin "1") (pinfunction "1_1") (pintype "passive"))
      (node (ref "C35") (pin "1") (pinfunction "1_1") (pintype "passive"))
      (node (ref "C37") (pin "1") (pinfunction "1_1") (pintype "passive"))
      (node (ref "C38") (pin "1") (pinfunction "1_1") (pintype "passive"))
      (node (ref "C39") (pin "2") (pinfunction "2_2") (pintype "passive"))
      (node (ref "C40") (pin "2") (pinfunction "2_2") (pintype "passive"))
      (node (ref "C41") (pin "2") (pinfunction "2_2") (pintype "passive"))
      (node (ref "C42") (pin "2") (pinfunction "2_2") (pintype "passive"))
      (node (ref "C43") (pin "1") (pinfunction "1_1") (pintype "passive"))
      (node (ref "C44") (pin "1") (pinfunction "1_1") (pintype "passive"))
      (node (ref "C45") (pin "1") (pinfunction "1_1") (pintype "passive"))
      (node (ref "C46") (pin "1") (pinfunction "1_1") (pintype "passive"))
      (node (ref "IC1") (pin "2") (pinfunction "3V3_2") (pintype "bidirectional"))
      (node (ref "IC3") (pin "2") (pinfunction "OUTPUT_1_2") (pintype "bidirectional"))
      (node (ref "IC3") (pin "4") (pinfunction "OUTPUT_2_4") (pintype "bidirectional"))
      (node (ref "IC4") (pin "2") (pinfunction "CSB_2") (pintype "bidirectional"))
      (node (ref "IC4") (pin "5") (pinfunction "SDO_5") (pintype "bidirectional"))
      (node (ref "IC4") (pin "6") (pinfunction "VDDIO_6") (pintype "bidirectional"))
      (node (ref "IC4") (pin "8") (pinfunction "VDD_8") (pintype "bidirectional"))
      (node (ref "IC6") (pin "12") (pinfunction "CS_12") (pintype "bidirectional"))
      (node (ref "IC6") (pin "5") (pinfunction "VDD_IO_5") (pintype "bidirectional"))
      (node (ref "IC6") (pin "8") (pinfunction "VDD_8") (pintype "bidirectional"))
      (node (ref "IC7") (pin "13") (pinfunction "VDDIO_13") (pintype "bidirectional"))
      (node (ref "IC7") (pin "2") (pinfunction "VDD_2") (pintype "bidirectional"))
      (node (ref "IC7") (pin "4") (pinfunction "SPI_CS_4") (pintype "bidirectional"))
      (node (ref "IC8") (pin "4") (pinfunction "VDD_4") (pintype "bidirectional"))
      (node (ref "IC9") (pin "2") (pinfunction "CSB_2") (pintype "bidirectional"))
      (node (ref "IC9") (pin "6") (pinfunction "VDDIO_6") (pintype "bidirectional"))
      (node (ref "IC9") (pin "8") (pinfunction "VDD_8") (pintype "bidirectional"))
      (node (ref "J1") (pin "4") (pinfunction "VDD_4") (pintype "bidirectional"))
      (node (ref "J2") (pin "2") (pinfunction "2_2") (pintype "power_in"))
      (node (ref "J3") (pin "2") (pinfunction "2_2") (pintype "power_in"))
      (node (ref "JP1") (pin "5") (pinfunction "5_5") (pintype "passive"))
      (node (ref "JP3") (pin "1") (pinfunction "1_1") (pintype "passive"))
      (node (ref "R1") (pin "1") (pinfunction "1_1") (pintype "passive"))
      (node (ref "R5") (pin "1") (pinfunction "1_1") (pintype "passive"))
      (node (ref "R6") (pin "1") (pinfunction "1_1") (pintype "passive"))
      (node (ref "R7") (pin "1") (pinfunction "1_1") (pintype "passive"))
      (node (ref "R8") (pin "1") (pinfunction "1_1") (pintype "passive"))
      (node (ref "TP12") (pin "TP") (pinfunction "TP_TP") (pintype "input"))
      (node (ref "TP5") (pin "TP") (pinfunction "TP_TP") (pintype "input"))
      (node (ref "U1") (pin "3") (pinfunction "3.3V_3") (pintype "power_in"))
    )
    (net (code "44") (name "GND") (class "Default")
      (node (ref "AC1") (pin "10") (pinfunction "RESERVED_1_10") (pintype "bidirectional"))
      (node (ref "AC1") (pin "12") (pinfunction "GND_2_12") (pintype "power_in"))
      (node (ref "AC1") (pin "13") (pinfunction "GND_3_13") (pintype "power_in"))
      (node (ref "AC1") (pin "16") (pinfunction "GND_4_16") (pintype "power_in"))
      (node (ref "AC1") (pin "5") (pinfunction "GND_1_5") (pintype "power_in"))
      (node (ref "AC1") (pin "7") (pinfunction "SDO_SA0_7") (pintype "bidirectional"))
      (node (ref "C1") (pin "2") (pinfunction "2_2") (pintype "passive"))
      (node (ref "C10") (pin "2") (pinfunction "2_2") (pintype "passive"))
      (node (ref "C11") (pin "2") (pinfunction "2_2") (pintype "passive"))
      (node (ref "C12") (pin "2") (pinfunction "2_2") (pintype "passive"))
      (node (ref "C13") (pin "2") (pinfunction "2_2") (pintype "passive"))
      (node (ref "C14") (pin "1") (pinfunction "1_1") (pintype "passive"))
      (node (ref "C15") (pin "1") (pinfunction "1_1") (pintype "passive"))
      (node (ref "C16") (pin "1") (pinfunction "1_1") (pintype "passive"))
      (node (ref "C17") (pin "1") (pinfunction "1_1") (pintype "passive"))
      (node (ref "C18") (pin "2") (pinfunction "2_2") (pintype "passive"))
      (node (ref "C19") (pin "2") (pinfunction "2_2") (pintype "passive"))
      (node (ref "C2") (pin "1") (pinfunction "1_1") (pintype "passive"))
      (node (ref "C20") (pin "1") (pinfunction "1_1") (pintype "passive"))
      (node (ref "C21") (pin "1") (pinfunction "1_1") (pintype "passive"))
      (node (ref "C22") (pin "1") (pinfunction "1_1") (pintype "passive"))
      (node (ref "C23") (pin "2") (pinfunction "2_2") (pintype "passive"))
      (node (ref "C24") (pin "2") (pinfunction "2_2") (pintype "passive"))
      (node (ref "C25") (pin "2") (pinfunction "2_2") (pintype "passive"))
      (node (ref "C26") (pin "2") (pinfunction "2_2") (pintype "passive"))
      (node (ref "C27") (pin "2") (pinfunction "2_2") (pintype "passive"))
      (node (ref "C28") (pin "2") (pinfunction "2_2") (pintype "passive"))
      (node (ref "C29") (pin "2") (pinfunction "2_2") (pintype "passive"))
      (node (ref "C3") (pin "2") (pinfunction "2_2") (pintype "passive"))
      (node (ref "C30") (pin "1") (pinfunction "1_1") (pintype "passive"))
      (node (ref "C31") (pin "1") (pinfunction "1_1") (pintype "passive"))
      (node (ref "C32") (pin "1") (pinfunction "1_1") (pintype "passive"))
      (node (ref "C33") (pin "1") (pinfunction "1_1") (pintype "passive"))
      (node (ref "C34") (pin "1") (pinfunction "1_1") (pintype "passive"))
      (node (ref "C35") (pin "2") (pinfunction "2_2") (pintype "passive"))
      (node (ref "C36") (pin "1") (pinfunction "1_1") (pintype "passive"))
      (node (ref "C37") (pin "2") (pinfunction "2_2") (pintype "passive"))
      (node (ref "C38") (pin "2") (pinfunction "2_2") (pintype "passive"))
      (node (ref "C39") (pin "1") (pinfunction "1_1") (pintype "passive"))
      (node (ref "C4") (pin "1") (pinfunction "1_1") (pintype "passive"))
      (node (ref "C40") (pin "1") (pinfunction "1_1") (pintype "passive"))
      (node (ref "C41") (pin "1") (pinfunction "1_1") (pintype "passive"))
      (node (ref "C42") (pin "1") (pinfunction "1_1") (pintype "passive"))
      (node (ref "C43") (pin "2") (pinfunction "2_2") (pintype "passive"))
      (node (ref "C44") (pin "2") (pinfunction "2_2") (pintype "passive"))
      (node (ref "C45") (pin "2") (pinfunction "2_2") (pintype "passive"))
      (node (ref "C46") (pin "2") (pinfunction "2_2") (pintype "passive"))
      (node (ref "C5") (pin "1") (pinfunction "1_1") (pintype "passive"))
      (node (ref "C6") (pin "1") (pinfunction "1_1") (pintype "passive"))
      (node (ref "C7") (pin "1") (pinfunction "1_1") (pintype "passive"))
      (node (ref "C8") (pin "2") (pinfunction "2_2") (pintype "passive"))
      (node (ref "C9") (pin "2") (pinfunction "2_2") (pintype "passive"))
      (node (ref "CN1") (pin "1") (pinfunction "2_1") (pintype "passive"))
      (node (ref "CN2") (pin "1") (pinfunction "2_1") (pintype "passive"))
      (node (ref "CN3") (pin "1") (pinfunction "2_1") (pintype "passive"))
      (node (ref "IC1") (pin "1") (pinfunction "GND_1_1") (pintype "bidirectional"))
      (node (ref "IC1") (pin "40") (pinfunction "GND_2_40") (pintype "bidirectional"))
      (node (ref "IC1") (pin "41") (pinfunction "GND_3_41") (pintype "bidirectional"))
      (node (ref "IC1") (pin "42") (pinfunction "GND_4_42") (pintype "bidirectional"))
      (node (ref "IC1") (pin "43") (pinfunction "GND_5_43") (pintype "bidirectional"))
      (node (ref "IC1") (pin "44") (pinfunction "GND_6_44") (pintype "bidirectional"))
      (node (ref "IC1") (pin "45") (pinfunction "GND_7_45") (pintype "bidirectional"))
      (node (ref "IC1") (pin "46") (pinfunction "GND_8_46") (pintype "bidirectional"))
      (node (ref "IC1") (pin "47") (pinfunction "GND_9_47") (pintype "bidirectional"))
      (node (ref "IC1") (pin "48") (pinfunction "GND_10_48") (pintype "bidirectional"))
      (node (ref "IC1") (pin "49") (pinfunction "GND_11_49") (pintype "bidirectional"))
      (node (ref "IC2") (pin "2") (pinfunction "GND_2") (pintype "bidirectional"))
      (node (ref "IC2") (pin "6") (pinfunction "FREQ_6") (pintype "bidirectional"))
      (node (ref "IC3") (pin "1") (pinfunction "GND_1") (pintype "bidirectional"))
      (node (ref "IC4") (pin "1") (pinfunction "GND_1_1") (pintype "bidirectional"))
      (node (ref "IC4") (pin "7") (pinfunction "GND_2_7") (pintype "bidirectional"))
      (node (ref "IC6") (pin "1") (pinfunction "SDO/SA0_1") (pintype "bidirectional"))
      (node (ref "IC6") (pin "2") (pinfunction "TDMOUT_2") (pintype "bidirectional"))
      (node (ref "IC6") (pin "3") (pinfunction "BCLK_3") (pintype "bidirectional"))
      (node (ref "IC6") (pin "6") (pinfunction "AH1/QVAR1_6") (pintype "bidirectional"))
      (node (ref "IC6") (pin "7") (pinfunction "GND_7") (pintype "bidirectional"))
      (node (ref "IC7") (pin "11") (pinfunction "GND_2_11") (pintype "bidirectional"))
      (node (ref "IC7") (pin "9") (pinfunction "GND_1_9") (pintype "bidirectional"))
      (node (ref "IC8") (pin "1") (pinfunction "GND_1") (pintype "bidirectional"))
      (node (ref "IC9") (pin "1") (pinfunction "GND_1_1") (pintype "bidirectional"))
      (node (ref "IC9") (pin "5") (pinfunction "SDO_5") (pintype "bidirectional"))
      (node (ref "IC9") (pin "7") (pinfunction "GND_2_7") (pintype "bidirectional"))
      (node (ref "J1") (pin "6") (pinfunction "VSS_6") (pintype "bidirectional"))
      (node (ref "J1") (pin "G1") (pinfunction "GND_1_G1") (pintype "bidirectional"))
      (node (ref "J1") (pin "G2") (pinfunction "GND_2_G2") (pintype "bidirectional"))
      (node (ref "J1") (pin "G3") (pinfunction "GND_3_G3") (pintype "bidirectional"))
      (node (ref "J1") (pin "G4") (pinfunction "GND_4_G4") (pintype "bidirectional"))
      (node (ref "J2") (pin "1") (pinfunction "1_1") (pintype "power_in"))
      (node (ref "J3") (pin "1") (pinfunction "1_1") (pintype "power_in"))
      (node (ref "J5") (pin "A1_B12") (pinfunction "GND_A1_B12") (pintype "power_in"))
      (node (ref "J5") (pin "B1_A12") (pinfunction "GND_B1_A12") (pintype "power_in"))
      (node (ref "J6") (pin "1") (pinfunction "1_1") (pintype "bidirectional"))
      (node (ref "JP1") (pin "1") (pinfunction "1_1") (pintype "passive"))
      (node (ref "JP2") (pin "2") (pinfunction "2_2") (pintype "passive"))
      (node (ref "JP3") (pin "4") (pinfunction "4_4") (pintype "passive"))
      (node (ref "JP4") (pin "1") (pinfunction "1_1") (pintype "passive"))
      (node (ref "JP5") (pin "1") (pinfunction "1_1") (pintype "passive"))
      (node (ref "LED2") (pin "C") (pinfunction "C_C") (pintype "passive"))
      (node (ref "LED3") (pin "C") (pinfunction "C_C") (pintype "passive"))
      (node (ref "R10") (pin "2") (pinfunction "2_2") (pintype "passive"))
      (node (ref "R11") (pin "1") (pinfunction "1_1") (pintype "passive"))
      (node (ref "R12") (pin "2") (pinfunction "2_2") (pintype "passive"))
      (node (ref "R13") (pin "2") (pinfunction "2_2") (pintype "passive"))
      (node (ref "R14") (pin "2") (pinfunction "2_2") (pintype "passive"))
      (node (ref "R15") (pin "2") (pinfunction "2_2") (pintype "passive"))
      (node (ref "R18") (pin "2") (pinfunction "2_2") (pintype "passive"))
      (node (ref "R19") (pin "2") (pinfunction "2_2") (pintype "passive"))
      (node (ref "R20") (pin "2") (pinfunction "2_2") (pintype "passive"))
      (node (ref "R3") (pin "2") (pinfunction "2_2") (pintype "passive"))
      (node (ref "R4") (pin "1") (pinfunction "1_1") (pintype "passive"))
      (node (ref "S1") (pin "C1") (pinfunction "NO_1_C1") (pintype "bidirectional"))
      (node (ref "S1") (pin "D1") (pinfunction "NO_2_D1") (pintype "bidirectional"))
      (node (ref "S2") (pin "C1") (pinfunction "NO_1_C1") (pintype "bidirectional"))
      (node (ref "S2") (pin "D1") (pinfunction "NO_2_D1") (pintype "bidirectional"))
      (node (ref "SIM7600G") (pin "1") (pinfunction "1_1") (pintype "passive"))
      (node (ref "SIM7600G") (pin "6") (pinfunction "6_6") (pintype "passive"))
      (node (ref "TP3") (pin "TP") (pinfunction "TP_TP") (pintype "input"))
      (node (ref "TP4") (pin "1") (pinfunction "TP_1") (pintype "passive"))
      (node (ref "U1") (pin "16") (pinfunction "GND_16") (pintype "power_in"))
      (node (ref "U1") (pin "2") (pinfunction "GND_2") (pintype "power_in"))
      (node (ref "U1") (pin "9") (pinfunction "GND_9") (pintype "power_in"))
    )
    (net (code "45") (name "Net-(D1-A)") (class "Default")
      (node (ref "C3") (pin "1") (pinfunction "1_1") (pintype "passive"))
      (node (ref "D1") (pin "2") (pinfunction "A_2") (pintype "bidirectional"))
      (node (ref "IC2") (pin "1") (pinfunction "SW_1") (pintype "bidirectional"))
      (node (ref "L1") (pin "1") (pinfunction "1_1") (pintype "bidirectional"))
    )
    (net (code "46") (name "Net-(IC2-FB)") (class "Default")
      (node (ref "IC2") (pin "3") (pinfunction "FB_3") (pintype "bidirectional"))
      (node (ref "R2") (pin "2") (pinfunction "2_2") (pintype "passive"))
      (node (ref "R3") (pin "1") (pinfunction "1_1") (pintype "passive"))
    )
    (net (code "47") (name "Net-(IC7-CAP)") (class "Default")
      (node (ref "C24") (pin "1") (pinfunction "1_1") (pintype "passive"))
      (node (ref "IC7") (pin "10") (pinfunction "CAP_10") (pintype "bidirectional"))
    )
    (net (code "48") (name "Net-(J1-PadCD1)") (class "Default")
      (node (ref "J1") (pin "CD1") (pinfunction "CD1_CD1") (pintype "bidirectional"))
      (node (ref "LED1") (pin "A") (pinfunction "A_A") (pintype "passive"))
    )
    (net (code "49") (name "Net-(LED1-PadC)") (class "Default")
      (node (ref "LED1") (pin "C") (pinfunction "C_C") (pintype "passive"))
      (node (ref "R15") (pin "1") (pinfunction "1_1") (pintype "passive"))
    )
    (net (code "50") (name "Net-(LED2-PadA)") (class "Default")
      (node (ref "LED2") (pin "A") (pinfunction "A_A") (pintype "passive"))
      (node (ref "R16") (pin "2") (pinfunction "2_2") (pintype "passive"))
    )
    (net (code "51") (name "Net-(LED3-PadA)") (class "Default")
      (node (ref "LED3") (pin "A") (pinfunction "A_A") (pintype "passive"))
      (node (ref "R17") (pin "2") (pinfunction "2_2") (pintype "passive"))
    )
    (net (code "52") (name "Net-(LED4-PadC)") (class "Default")
      (node (ref "LED4") (pin "C") (pinfunction "C_C") (pintype "passive"))
      (node (ref "R18") (pin "1") (pinfunction "1_1") (pintype "passive"))
    )
    (net (code "53") (name "Net-(LED5-PadC)") (class "Default")
      (node (ref "LED5") (pin "C") (pinfunction "C_C") (pintype "passive"))
      (node (ref "R19") (pin "1") (pinfunction "1_1") (pintype "passive"))
    )
    (net (code "54") (name "Net-(LED6-PadC)") (class "Default")
      (node (ref "LED6") (pin "C") (pinfunction "C_C") (pintype "passive"))
      (node (ref "R20") (pin "1") (pinfunction "1_1") (pintype "passive"))
    )
    (net (code "55") (name "unconnected-(AC1-INT1-Pad11)") (class "Default")
      (node (ref "AC1") (pin "11") (pinfunction "INT1_11") (pintype "input"))
    )
    (net (code "56") (name "unconnected-(AC1-INT2-Pad9)") (class "Default")
      (node (ref "AC1") (pin "9") (pinfunction "INT2_9") (pintype "input"))
    )
    (net (code "57") (name "unconnected-(AC1-NC_1-Pad2)") (class "Default")
      (node (ref "AC1") (pin "2") (pinfunction "NC_1_2") (pintype "bidirectional"))
    )
    (net (code "58") (name "unconnected-(AC1-NC_2-Pad3)") (class "Default")
      (node (ref "AC1") (pin "3") (pinfunction "NC_2_3") (pintype "bidirectional"))
    )
    (net (code "59") (name "unconnected-(IC1-IO3-Pad15)") (class "Default")
      (node (ref "IC1") (pin "15") (pinfunction "IO3_15") (pintype "bidirectional"))
    )
    (net (code "60") (name "unconnected-(IC1-IO45-Pad26)") (class "Default")
      (node (ref "IC1") (pin "26") (pinfunction "IO45_26") (pintype "bidirectional"))
    )
    (net (code "61") (name "unconnected-(IC1-IO46-Pad16)") (class "Default")
      (node (ref "IC1") (pin "16") (pinfunction "IO46_16") (pintype "bidirectional"))
    )
    (net (code "62") (name "unconnected-(IC6-AH2{slash}QVAR2-Pad9)") (class "Default")
      (node (ref "IC6") (pin "9") (pinfunction "AH2/QVAR2_9") (pintype "bidirectional"))
    )
    (net (code "63") (name "unconnected-(IC6-INT1-Pad4)") (class "Default")
      (node (ref "IC6") (pin "4") (pinfunction "INT1_4") (pintype "bidirectional"))
    )
    (net (code "64") (name "unconnected-(IC6-INT2-Pad10)") (class "Default")
      (node (ref "IC6") (pin "10") (pinfunction "INT2_10") (pintype "bidirectional"))
    )
    (net (code "65") (name "unconnected-(IC6-WCLK-Pad11)") (class "Default")
      (node (ref "IC6") (pin "11") (pinfunction "WCLK_11") (pintype "bidirectional"))
    )
    (net (code "66") (name "unconnected-(IC7-INT-Pad15)") (class "Default")
      (node (ref "IC7") (pin "15") (pinfunction "INT_15") (pintype "bidirectional"))
    )
    (net (code "67") (name "unconnected-(IC7-NC_1-Pad3)") (class "Default")
      (node (ref "IC7") (pin "3") (pinfunction "NC_1_3") (pintype "bidirectional"))
    )
    (net (code "68") (name "unconnected-(IC7-NC_2-Pad6)") (class "Default")
      (node (ref "IC7") (pin "6") (pinfunction "NC_2_6") (pintype "bidirectional"))
    )
    (net (code "69") (name "unconnected-(IC7-NC_3-Pad7)") (class "Default")
      (node (ref "IC7") (pin "7") (pinfunction "NC_3_7") (pintype "bidirectional"))
    )
    (net (code "70") (name "unconnected-(IC7-NC_4-Pad8)") (class "Default")
      (node (ref "IC7") (pin "8") (pinfunction "NC_4_8") (pintype "bidirectional"))
    )
    (net (code "71") (name "unconnected-(IC7-NC_5-Pad12)") (class "Default")
      (node (ref "IC7") (pin "12") (pinfunction "NC_5_12") (pintype "bidirectional"))
    )
    (net (code "72") (name "unconnected-(IC7-NC_6-Pad14)") (class "Default")
      (node (ref "IC7") (pin "14") (pinfunction "NC_6_14") (pintype "bidirectional"))
    )
    (net (code "73") (name "unconnected-(IC7-SPI_SDO-Pad5)") (class "Default")
      (node (ref "IC7") (pin "5") (pinfunction "SPI_SDO_5") (pintype "bidirectional"))
    )
    (net (code "74") (name "unconnected-(IC8-INT-Pad2)") (class "Default")
      (node (ref "IC8") (pin "2") (pinfunction "INT_2") (pintype "bidirectional"))
    )
    (net (code "75") (name "unconnected-(IC8-NC-Pad3)") (class "Default")
      (node (ref "IC8") (pin "3") (pinfunction "NC_3") (pintype "no_connect"))
    )
    (net (code "76") (name "unconnected-(J1-DAT1-Pad8)") (class "Default")
      (node (ref "J1") (pin "8") (pinfunction "DAT1_8") (pintype "bidirectional"))
    )
    (net (code "77") (name "unconnected-(J1-DAT2-Pad1)") (class "Default")
      (node (ref "J1") (pin "1") (pinfunction "DAT2_1") (pintype "bidirectional"))
    )
    (net (code "78") (name "unconnected-(J5-SBU1-PadA8)") (class "Default")
      (node (ref "J5") (pin "A8") (pinfunction "SBU1_A8") (pintype "bidirectional"))
    )
    (net (code "79") (name "unconnected-(J5-SBU2-PadB8)") (class "Default")
      (node (ref "J5") (pin "B8") (pinfunction "SBU2_B8") (pintype "bidirectional"))
    )
    (net (code "80") (name "unconnected-(JP1-Pad2)") (class "Default")
      (node (ref "JP1") (pin "2") (pinfunction "2_2") (pintype "passive"))
    )
    (net (code "81") (name "unconnected-(U1-ANT-Pad1)") (class "Default")
      (node (ref "U1") (pin "1") (pinfunction "ANT_1") (pintype "bidirectional"))
    )
  )
)
